# Sheet1.net
KiCad netlist of a schematic drawn in Altium Designer
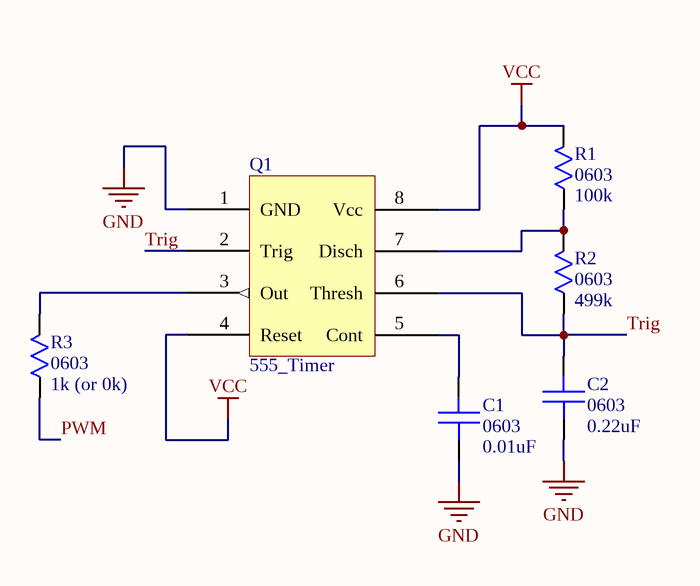
[diagram p0: Sheet1.SchDoc]

(export (version "E")
  (design (tool "Eeschema 10.0.6"))
  (components
    (comp (ref "C1")
      (value "0603")
      (footprint "0603")
      (description "0603 capacitor")
      (fields (field (name "ALTIUM_VALUE") "0.01uF"))
      (libsource (lib "NewLibrary") (part "Capacitor"))
    )
    (comp (ref "C2")
      (value "0603")
      (footprint "0603")
      (description "0603 capacitor")
      (fields (field (name "ALTIUM_VALUE") "0.22uF"))
      (libsource (lib "NewLibrary") (part "Capacitor"))
    )
    (comp (ref "Q1")
      (value "555_Timer")
      (footprint "DIP8")
      (libsource (lib "NewLibrary") (part "555_Timer_PDIP"))
    )
    (comp (ref "R1")
      (value "0603")
      (footprint "0603")
      (description "0603 resistor")
      (fields (field (name "ALTIUM_VALUE") "100k"))
      (libsource (lib "NewLibrary") (part "Resistor"))
    )
    (comp (ref "R2")
      (value "0603")
      (footprint "0603")
      (description "0603 resistor")
      (fields (field (name "ALTIUM_VALUE") "499k"))
      (libsource (lib "NewLibrary") (part "Resistor"))
    )
    (comp (ref "R3")
      (value "0603")
      (footprint "0603")
      (description "0603 resistor")
      (fields (field (name "ALTIUM_VALUE") "1k (or 0k)"))
      (libsource (lib "NewLibrary") (part "Resistor"))
    )
  )
  (nets
    (net (code "1") (name "/PWM") (class "Default")
      (node (ref "R3") (pin "1") (pinfunction "1_1") (pintype "passive"))
    )
    (net (code "2") (name "/Trig") (class "Default")
      (node (ref "C2") (pin "2") (pinfunction "2_2") (pintype "passive"))
      (node (ref "Q1") (pin "2") (pinfunction "Trig_2") (pintype "passive"))
      (node (ref "Q1") (pin "6") (pinfunction "Thresh_6") (pintype "passive"))
      (node (ref "R2") (pin "1") (pinfunction "1_1") (pintype "passive"))
    )
    (net (code "3") (name "GND") (class "Default")
      (node (ref "C1") (pin "1") (pinfunction "1_1") (pintype "passive"))
      (node (ref "C2") (pin "1") (pinfunction "1_1") (pintype "passive"))
      (node (ref "Q1") (pin "1") (pinfunction "GND_1") (pintype "passive"))
    )
    (net (code "4") (name "Net-(Q1-Cont)") (class "Default")
      (node (ref "C1") (pin "2") (pinfunction "2_2") (pintype "passive"))
      (node (ref "Q1") (pin "5") (pinfunction "Cont_5") (pintype "passive"))
    )
    (net (code "5") (name "Net-(Q1-Disch)") (class "Default")
      (node (ref "Q1") (pin "7") (pinfunction "Disch_7") (pintype "passive"))
      (node (ref "R1") (pin "1") (pinfunction "1_1") (pintype "passive"))
      (node (ref "R2") (pin "2") (pinfunction "2_2") (pintype "passive"))
    )
    (net (code "6") (name "Net-(Q1-Out)") (class "Default")
      (node (ref "Q1") (pin "3") (pinfunction "Out_3") (pintype "output"))
      (node (ref "R3") (pin "2") (pinfunction "2_2") (pintype "passive"))
    )
    (net (code "7") (name "VCC") (class "Default")
      (node (ref "Q1") (pin "4") (pinfunction "Reset_4") (pintype "passive"))
      (node (ref "Q1") (pin "8") (pinfunction "Vcc_8") (pintype "power_in"))
      (node (ref "R1") (pin "2") (pinfunction "2_2") (pintype "passive"))
    )
  )
)
